# SCH3_Microcontroller.net
KiCad netlist of a schematic drawn in Altium Designer
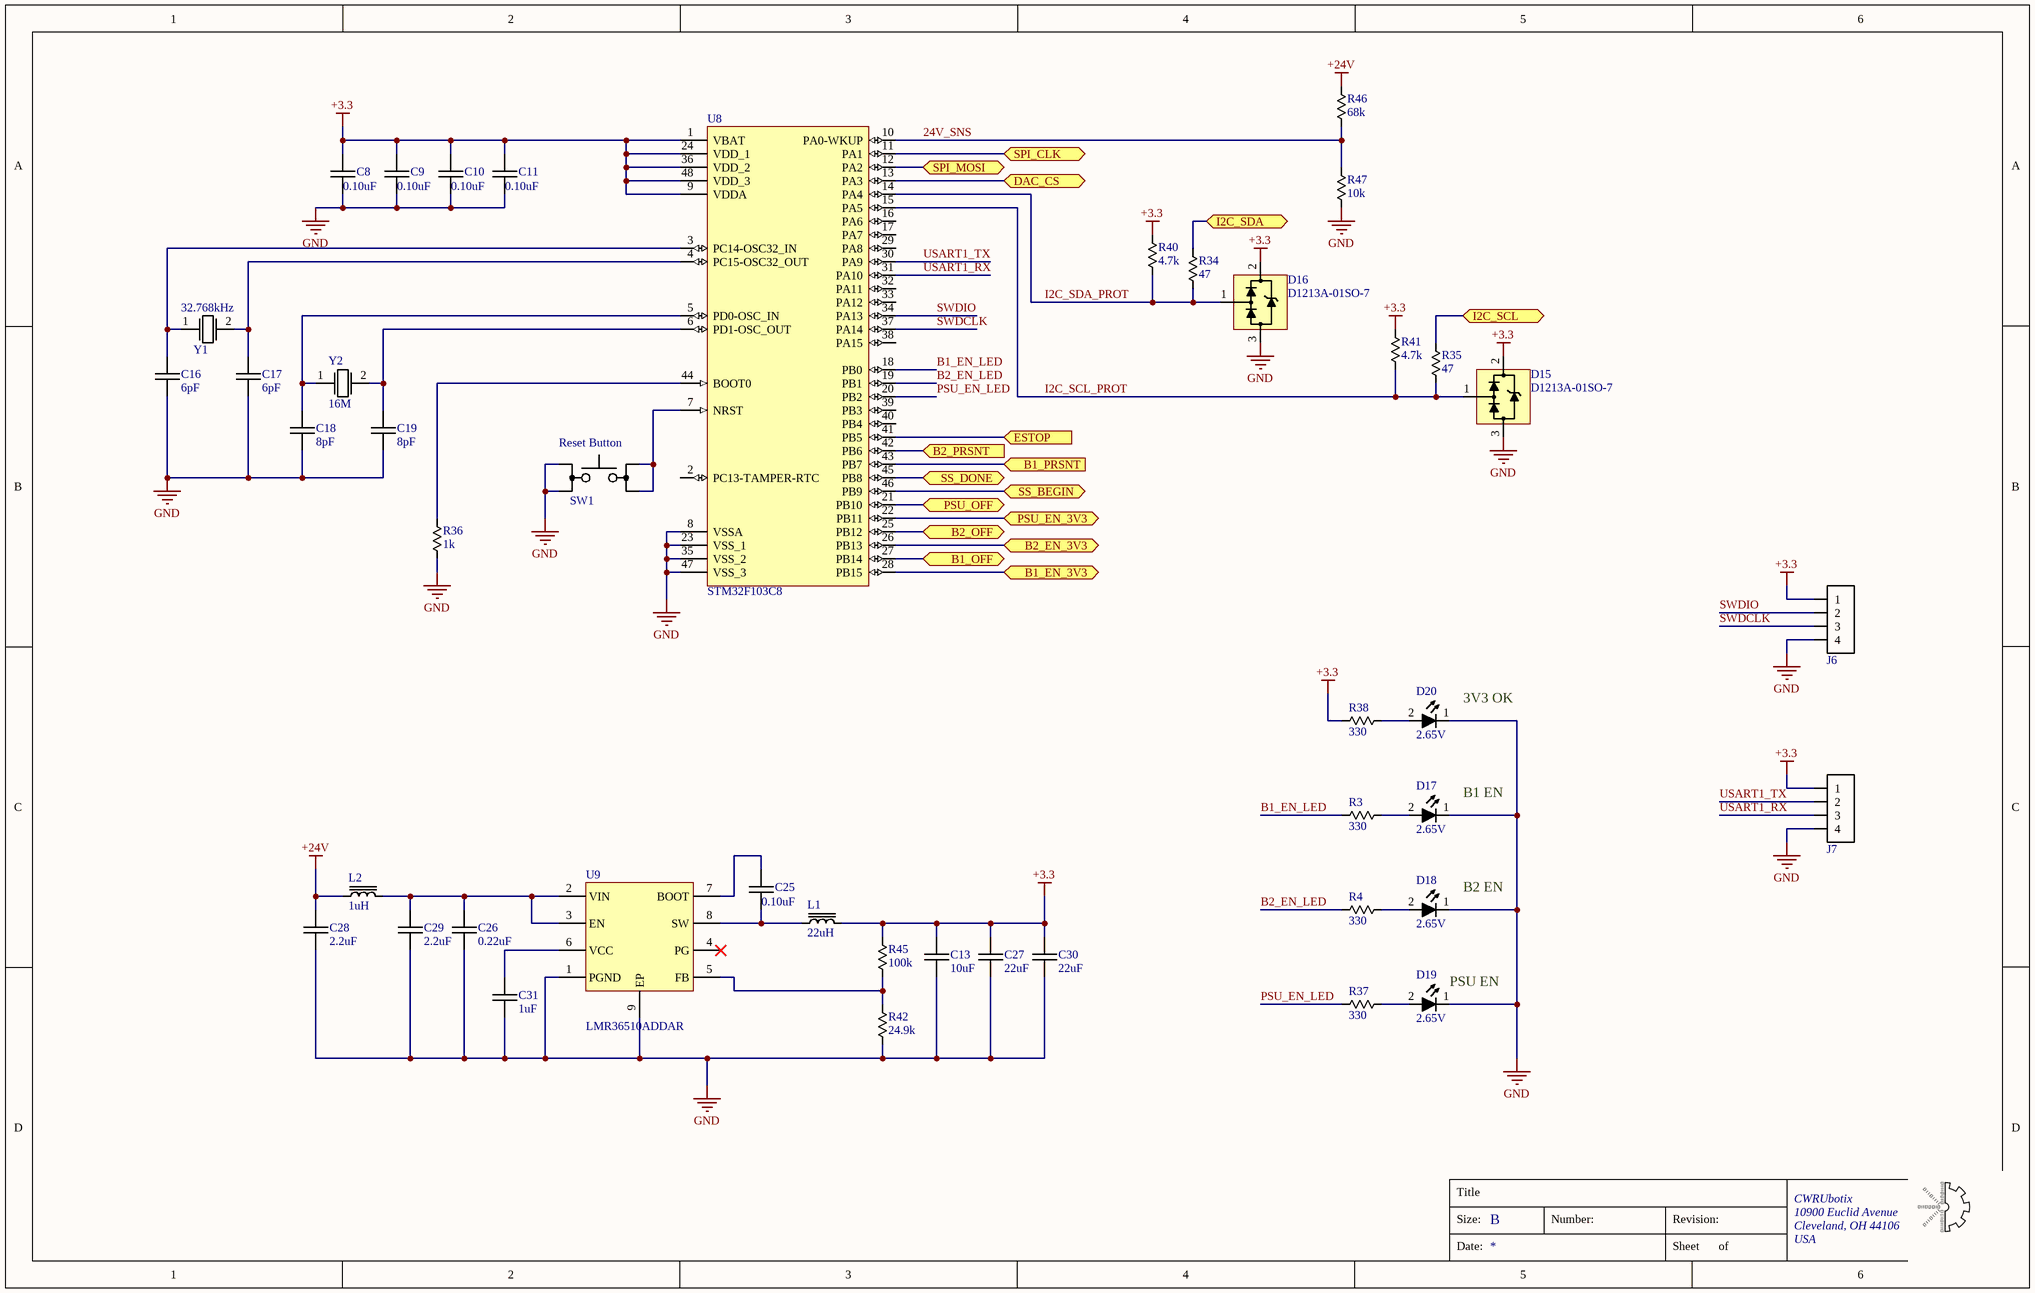
[diagram p0: SCH3_Microcontroller.SchDoc]

(export (version "E")
  (design (tool "Eeschema 10.0.6"))
  (components
    (comp (ref "C8")
      (value "0.10uF")
      (footprint "chip_0805")
      (description "CAP, 0.10uF, 10%, 16V, X7R, 0805")
      (fields (field (name "PART NUMBER") "CAP-00069") (field (name "TOLERANCE") "10%"))
      (libsource (lib "Capacitors$") (part "CAP-00069"))
    )
    (comp (ref "C9")
      (value "0.10uF")
      (footprint "chip_0805")
      (description "CAP, 0.10uF, 10%, 16V, X7R, 0805")
      (fields (field (name "PART NUMBER") "CAP-00069") (field (name "TOLERANCE") "10%"))
      (libsource (lib "Capacitors$") (part "CAP-00069"))
    )
    (comp (ref "C10")
      (value "0.10uF")
      (footprint "chip_0805")
      (description "CAP, 0.10uF, 10%, 16V, X7R, 0805")
      (fields (field (name "PART NUMBER") "CAP-00069") (field (name "TOLERANCE") "10%"))
      (libsource (lib "Capacitors$") (part "CAP-00069"))
    )
    (comp (ref "C11")
      (value "0.10uF")
      (footprint "chip_0805")
      (description "CAP, 0.10uF, 10%, 16V, X7R, 0805")
      (fields (field (name "PART NUMBER") "CAP-00069") (field (name "TOLERANCE") "10%"))
      (libsource (lib "Capacitors$") (part "CAP-00069"))
    )
    (comp (ref "C13")
      (value "10uF")
      (footprint "chip_1206")
      (description "CAP, 10uF, ±10%, 25V, X7R, 1206")
      (fields (field (name "PART NUMBER") "CAP-00539") (field (name "TOLERANCE") "±10%"))
      (libsource (lib "Capacitors$") (part "CAP-00539"))
    )
    (comp (ref "C16")
      (value "6pF")
      (footprint "chip_0603")
      (description "CAP, 6pF, ±10%, 50V, C0G, 0603")
      (fields (field (name "PART NUMBER") "CAP-00538") (field (name "TOLERANCE") "±10%"))
      (libsource (lib "Capacitors$") (part "CAP-00538"))
    )
    (comp (ref "C17")
      (value "6pF")
      (footprint "chip_0603")
      (description "CAP, 6pF, ±10%, 50V, C0G, 0603")
      (fields (field (name "PART NUMBER") "CAP-00538") (field (name "TOLERANCE") "±10%"))
      (libsource (lib "Capacitors$") (part "CAP-00538"))
    )
    (comp (ref "C18")
      (value "8pF")
      (footprint "chip_0603")
      (description "CAP, 8pF, ±0.1pF, 50V, C0G, 0603")
      (fields (field (name "PART NUMBER") "CAP-00402") (field (name "TOLERANCE") "±0.1pF"))
      (libsource (lib "Capacitors$") (part "CAP-00402"))
    )
    (comp (ref "C19")
      (value "8pF")
      (footprint "chip_0603")
      (description "CAP, 8pF, ±0.1pF, 50V, C0G, 0603")
      (fields (field (name "PART NUMBER") "CAP-00402") (field (name "TOLERANCE") "±0.1pF"))
      (libsource (lib "Capacitors$") (part "CAP-00402"))
    )
    (comp (ref "C25")
      (value "0.10uF")
      (footprint "chip_0805")
      (description "CAP, 0.10uF, 10%, 16V, X7R, 0805")
      (fields (field (name "PART NUMBER") "CAP-00069") (field (name "TOLERANCE") "10%"))
      (libsource (lib "Capacitors$") (part "CAP-00069"))
    )
    (comp (ref "C26")
      (value "0.22uF")
      (footprint "chip_0805")
      (description "CAP, 0.22uF, 10%, 100V, X7R, 0805")
      (fields (field (name "PART NUMBER") "CAP-00080") (field (name "TOLERANCE") "10%"))
      (libsource (lib "Capacitors$") (part "CAP-00080"))
    )
    (comp (ref "C27")
      (value "22uF")
      (footprint "chip_1206")
      (description "CAP, 22uF, ±10%, 25V, X5R, 1206")
      (fields (field (name "PART NUMBER") "CAP-00587") (field (name "TOLERANCE") "±10%"))
      (libsource (lib "Capacitors$") (part "CAP-00587"))
    )
    (comp (ref "C28")
      (value "2.2uF")
      (footprint "chip_1206")
      (description "CAP, 2.2uF, ±10%, 50V, X7R, 1206")
      (fields (field (name "PART NUMBER") "CAP-00563") (field (name "TOLERANCE") "±10%"))
      (libsource (lib "Capacitors$") (part "CAP-00563"))
    )
    (comp (ref "C29")
      (value "2.2uF")
      (footprint "chip_1206")
      (description "CAP, 2.2uF, ±10%, 50V, X7R, 1206")
      (fields (field (name "PART NUMBER") "CAP-00563") (field (name "TOLERANCE") "±10%"))
      (libsource (lib "Capacitors$") (part "CAP-00563"))
    )
    (comp (ref "C30")
      (value "22uF")
      (footprint "chip_1206")
      (description "CAP, 22uF, ±10%, 25V, X5R, 1206")
      (fields (field (name "PART NUMBER") "CAP-00587") (field (name "TOLERANCE") "±10%"))
      (libsource (lib "Capacitors$") (part "CAP-00587"))
    )
    (comp (ref "C31")
      (value "1uF")
      (footprint "chip_0805")
      (description "CAP, 1uF, 10%, 16V, X7R, 0805")
      (fields (field (name "PART NUMBER") "CAP-00107") (field (name "TOLERANCE") "10%"))
      (libsource (lib "Capacitors$") (part "CAP-00107"))
    )
    (comp (ref "D15")
      (value "D1213A-01SO-7")
      (footprint "SOT-23-3_1")
      (description "TVS, Rail-Rail Steering + Zener Clamp, 3.3V Standoff, 10V Clamping")
      (fields (field (name "PART NUMBER") "DIO-00075") (field (name "MANUFACTURER") "Diodes Incorporated"))
      (libsource (lib "Diodes$") (part "DIO-00075"))
    )
    (comp (ref "D16")
      (value "D1213A-01SO-7")
      (footprint "SOT-23-3_1")
      (description "TVS, Rail-Rail Steering + Zener Clamp, 3.3V Standoff, 10V Clamping")
      (fields (field (name "PART NUMBER") "DIO-00075") (field (name "MANUFACTURER") "Diodes Incorporated"))
      (libsource (lib "Diodes$") (part "DIO-00075"))
    )
    (comp (ref "D17")
      (value "2.65V")
      (footprint "chip_0603_LED")
      (description "LED, Blue, 0603, Low current, HELI2 Series")
      (fields (field (name "PART NUMBER") "DIO-00049") (field (name "MANUFACTURER") "Kingbright"))
      (libsource (lib "Diodes$") (part "DIO-00049"))
    )
    (comp (ref "D18")
      (value "2.65V")
      (footprint "chip_0603_LED")
      (description "LED, Blue, 0603, Low current, HELI2 Series")
      (fields (field (name "PART NUMBER") "DIO-00049") (field (name "MANUFACTURER") "Kingbright"))
      (libsource (lib "Diodes$") (part "DIO-00049"))
    )
    (comp (ref "D19")
      (value "2.65V")
      (footprint "chip_0603_LED")
      (description "LED, Blue, 0603, Low current, HELI2 Series")
      (fields (field (name "PART NUMBER") "DIO-00049") (field (name "MANUFACTURER") "Kingbright"))
      (libsource (lib "Diodes$") (part "DIO-00049"))
    )
    (comp (ref "D20")
      (value "2.65V")
      (footprint "chip_0603_LED")
      (description "LED, Blue, 0603, Low current, HELI2 Series")
      (fields (field (name "PART NUMBER") "DIO-00049") (field (name "MANUFACTURER") "Kingbright"))
      (libsource (lib "Diodes$") (part "DIO-00049"))
    )
    (comp (ref "J6")
      (value "conn-4x1_0")
      (footprint "HDDR_4x1_0")
      (description "Header 4x1, 0.1\"")
      (fields (field (name "PART NUMBER") "CONN-00029"))
      (libsource (lib "Connectors$") (part "CONN-00029"))
    )
    (comp (ref "J7")
      (value "conn-4x1_0")
      (footprint "HDDR_4x1_0")
      (description "Header 4x1, 0.1\"")
      (fields (field (name "PART NUMBER") "CONN-00029"))
      (libsource (lib "Connectors$") (part "CONN-00029"))
    )
    (comp (ref "L1")
      (value "22uH")
      (footprint "BOURNS_SRN5040")
      (description "Ind, 10uH, 2.1A (2.3A sat.), 0.068 Ohm, SMD")
      (fields (field (name "PART NUMBER") "MAG-00129") (field (name "TOLERANCE") "20%"))
      (libsource (lib "Magnetics$") (part "MAG-00129"))
    )
    (comp (ref "L2")
      (value "1uH")
      (footprint "chip_0805")
      (description "Ind, 1uH, 20%, 900mA, 0805")
      (fields (field (name "PART NUMBER") "MAG-00009") (field (name "TOLERANCE") "20%"))
      (libsource (lib "Magnetics$") (part "MAG-00009"))
    )
    (comp (ref "R3")
      (value "330")
      (footprint "chip_0805")
      (description "RES SMD 330 OHM 1% 1/8W 0805")
      (fields (field (name "PART NUMBER") "RES-00222") (field (name "TOLERANCE") "1%"))
      (libsource (lib "Resistors$") (part "RES-00222"))
    )
    (comp (ref "R4")
      (value "330")
      (footprint "chip_0805")
      (description "RES SMD 330 OHM 1% 1/8W 0805")
      (fields (field (name "PART NUMBER") "RES-00222") (field (name "TOLERANCE") "1%"))
      (libsource (lib "Resistors$") (part "RES-00222"))
    )
    (comp (ref "R34")
      (value "47")
      (footprint "chip_0805")
      (description "RES SMD 47 OHM 1% 1/8W 0805")
      (fields (field (name "PART NUMBER") "RES-00154") (field (name "TOLERANCE") "1%"))
      (libsource (lib "Resistors$") (part "RES-00154"))
    )
    (comp (ref "R35")
      (value "47")
      (footprint "chip_0805")
      (description "RES SMD 47 OHM 1% 1/8W 0805")
      (fields (field (name "PART NUMBER") "RES-00154") (field (name "TOLERANCE") "1%"))
      (libsource (lib "Resistors$") (part "RES-00154"))
    )
    (comp (ref "R36")
      (value "1k")
      (footprint "chip_0805")
      (description "RES SMD 1K OHM 1% 1/8W 0805")
      (fields (field (name "PART NUMBER") "RES-00361") (field (name "TOLERANCE") "1%"))
      (libsource (lib "Resistors$") (part "RES-00361"))
    )
    (comp (ref "R37")
      (value "330")
      (footprint "chip_0805")
      (description "RES SMD 330 OHM 1% 1/8W 0805")
      (fields (field (name "PART NUMBER") "RES-00222") (field (name "TOLERANCE") "1%"))
      (libsource (lib "Resistors$") (part "RES-00222"))
    )
    (comp (ref "R38")
      (value "330")
      (footprint "chip_0805")
      (description "RES SMD 330 OHM 1% 1/8W 0805")
      (fields (field (name "PART NUMBER") "RES-00222") (field (name "TOLERANCE") "1%"))
      (libsource (lib "Resistors$") (part "RES-00222"))
    )
    (comp (ref "R40")
      (value "4.7k")
      (footprint "chip_0805")
      (description "RES SMD 4.7K OHM 1% 1/8W 0805")
      (fields (field (name "PART NUMBER") "RES-00471") (field (name "TOLERANCE") "1%"))
      (libsource (lib "Resistors$") (part "RES-00471"))
    )
    (comp (ref "R41")
      (value "4.7k")
      (footprint "chip_0805")
      (description "RES SMD 4.7K OHM 1% 1/8W 0805")
      (fields (field (name "PART NUMBER") "RES-00471") (field (name "TOLERANCE") "1%"))
      (libsource (lib "Resistors$") (part "RES-00471"))
    )
    (comp (ref "R42")
      (value "24.9k")
      (footprint "chip_0805")
      (description "RES SMD 24.9K OHM 1% 1/8W 0805")
      (fields (field (name "PART NUMBER") "RES-00396") (field (name "TOLERANCE") "1%"))
      (libsource (lib "Resistors$") (part "RES-00396"))
    )
    (comp (ref "R45")
      (value "100k")
      (footprint "chip_0805")
      (description "RES SMD 100K OHM 1% 1/8W 0805")
      (fields (field (name "PART NUMBER") "RES-00302") (field (name "TOLERANCE") "1%"))
      (libsource (lib "Resistors$") (part "RES-00302"))
    )
    (comp (ref "R46")
      (value "68k")
      (footprint "chip_0805")
      (description "RES SMD 68K OHM 1% 1/8W 0805 100ppm")
      (fields (field (name "PART NUMBER") "RES-00724") (field (name "TOLERANCE") "1%"))
      (libsource (lib "Resistors$") (part "RES-00724"))
    )
    (comp (ref "R47")
      (value "10k")
      (footprint "chip_0805")
      (description "RES SMD 10K OHM 1% 1/8W 0805")
      (fields (field (name "PART NUMBER") "RES-00307") (field (name "TOLERANCE") "1%"))
      (libsource (lib "Resistors$") (part "RES-00307"))
    )
    (comp (ref "SW1")
      (value "SW_1P1T_2")
      (footprint "TE_CONN_3-1825910-5")
      (description "Switch, Tactile, SPST-NO, 50mA 24V, Vertical, Thru-Hole")
      (fields (field (name "PART NUMBER") "MISC-00059") (field (name "MANUFACTURER") "TE Connectivity"))
      (libsource (lib "Misc$") (part "MISC-00059"))
    )
    (comp (ref "U8")
      (value "STM32F103C8")
      (footprint "LQFP48_0")
      (description "STM32 M3, LQFP-48")
      (fields (field (name "PART NUMBER") "UCTRL-00008") (field (name "MANUFACTURER") "ST"))
      (libsource (lib "Microcontrollers$") (part "UCTRL-00008"))
    )
    (comp (ref "U9")
      (value "LMR36510ADDAR")
      (footprint "SO-8_PPAD")
      (description "REG, Synchronous Buck, 4.2V~65V, 1A, Simple Switcher")
      (fields (field (name "PART NUMBER") "PWREG-00076") (field (name "MANUFACTURER") "TI"))
      (libsource (lib "Power Reg$") (part "PWREG-00076"))
    )
    (comp (ref "Y1")
      (value "osc_xtal_2p_0")
      (footprint "ABS25_OSC")
      (description "XTAL, 32.768kHz, 6pF, 20ppm")
      (fields (field (name "PART NUMBER") "OSC-00003") (field (name "TOLERANCE") "20ppm"))
      (libsource (lib "Oscillators$") (part "OSC-00003"))
    )
    (comp (ref "Y2")
      (value "16M")
      (footprint "NX5032GA")
      (description "XTAL, 16MHz, 8pF, 50, 20ppm")
      (fields (field (name "PART NUMBER") "OSC-00000") (field (name "TOLERANCE") "20ppm"))
      (libsource (lib "Oscillators$") (part "OSC-00000"))
    )
  )
  (nets
    (net (code "1") (name "+3.3") (class "Default")
      (node (ref "C10") (pin "1") (pinfunction "1_1") (pintype "passive"))
      (node (ref "C11") (pin "1") (pinfunction "1_1") (pintype "passive"))
      (node (ref "C13") (pin "1") (pinfunction "1_1") (pintype "passive"))
      (node (ref "C27") (pin "1") (pinfunction "1_1") (pintype "passive"))
      (node (ref "C30") (pin "1") (pinfunction "1_1") (pintype "passive"))
      (node (ref "C8") (pin "1") (pinfunction "1_1") (pintype "passive"))
      (node (ref "C9") (pin "1") (pinfunction "1_1") (pintype "passive"))
      (node (ref "D15") (pin "2") (pinfunction "VCC_2") (pintype "passive"))
      (node (ref "D16") (pin "2") (pinfunction "VCC_2") (pintype "passive"))
      (node (ref "J6") (pin "1") (pinfunction "1_1") (pintype "passive"))
      (node (ref "J7") (pin "1") (pinfunction "1_1") (pintype "passive"))
      (node (ref "L1") (pin "2") (pinfunction "2_2") (pintype "passive"))
      (node (ref "R38") (pin "1") (pinfunction "1_1") (pintype "passive"))
      (node (ref "R40") (pin "1") (pinfunction "1_1") (pintype "passive"))
      (node (ref "R41") (pin "1") (pinfunction "1_1") (pintype "passive"))
      (node (ref "R45") (pin "2") (pinfunction "2_2") (pintype "passive"))
      (node (ref "U8") (pin "1") (pinfunction "VBAT_1") (pintype "passive"))
      (node (ref "U8") (pin "24") (pinfunction "VDD_1_24") (pintype "power_in"))
      (node (ref "U8") (pin "36") (pinfunction "VDD_2_36") (pintype "power_in"))
      (node (ref "U8") (pin "48") (pinfunction "VDD_3_48") (pintype "power_in"))
      (node (ref "U8") (pin "9") (pinfunction "VDDA_9") (pintype "power_in"))
    )
    (net (code "2") (name "+24V") (class "Default")
      (node (ref "C28") (pin "1") (pinfunction "1_1") (pintype "passive"))
      (node (ref "L2") (pin "1") (pinfunction "1_1") (pintype "passive"))
      (node (ref "R46") (pin "1") (pinfunction "1_1") (pintype "passive"))
    )
    (net (code "3") (name "/24V_SNS") (class "Default")
      (node (ref "R46") (pin "2") (pinfunction "2_2") (pintype "passive"))
      (node (ref "R47") (pin "1") (pinfunction "1_1") (pintype "passive"))
      (node (ref "U8") (pin "10") (pinfunction "PA0-WKUP_10") (pintype "bidirectional"))
    )
    (net (code "4") (name "/B1_EN_3V3") (class "Default")
      (node (ref "U8") (pin "28") (pinfunction "PB15_28") (pintype "bidirectional"))
    )
    (net (code "5") (name "/B1_EN_LED") (class "Default")
      (node (ref "R3") (pin "1") (pinfunction "1_1") (pintype "passive"))
      (node (ref "U8") (pin "18") (pinfunction "PB0_18") (pintype "bidirectional"))
    )
    (net (code "6") (name "/B1_OFF") (class "Default")
      (node (ref "U8") (pin "27") (pinfunction "PB14_27") (pintype "bidirectional"))
    )
    (net (code "7") (name "/B1_PRSNT") (class "Default")
      (node (ref "U8") (pin "43") (pinfunction "PB7_43") (pintype "bidirectional"))
    )
    (net (code "8") (name "/B2_EN_3V3") (class "Default")
      (node (ref "U8") (pin "26") (pinfunction "PB13_26") (pintype "bidirectional"))
    )
    (net (code "9") (name "/B2_EN_LED") (class "Default")
      (node (ref "R4") (pin "1") (pinfunction "1_1") (pintype "passive"))
      (node (ref "U8") (pin "19") (pinfunction "PB1_19") (pintype "bidirectional"))
    )
    (net (code "10") (name "/B2_OFF") (class "Default")
      (node (ref "U8") (pin "25") (pinfunction "PB12_25") (pintype "bidirectional"))
    )
    (net (code "11") (name "/B2_PRSNT") (class "Default")
      (node (ref "U8") (pin "42") (pinfunction "PB6_42") (pintype "bidirectional"))
    )
    (net (code "12") (name "/DAC_CS") (class "Default")
      (node (ref "U8") (pin "13") (pinfunction "PA3_13") (pintype "bidirectional"))
    )
    (net (code "13") (name "/ESTOP") (class "Default")
      (node (ref "U8") (pin "41") (pinfunction "PB5_41") (pintype "bidirectional"))
    )
    (net (code "14") (name "/I2C_SCL") (class "Default")
      (node (ref "R35") (pin "2") (pinfunction "2_2") (pintype "passive"))
    )
    (net (code "15") (name "/I2C_SCL_PROT") (class "Default")
      (node (ref "D15") (pin "1") (pinfunction "LINE_1") (pintype "passive"))
      (node (ref "R35") (pin "1") (pinfunction "1_1") (pintype "passive"))
      (node (ref "R41") (pin "2") (pinfunction "2_2") (pintype "passive"))
      (node (ref "U8") (pin "15") (pinfunction "PA5_15") (pintype "bidirectional"))
    )
    (net (code "16") (name "/I2C_SDA") (class "Default")
      (node (ref "R34") (pin "2") (pinfunction "2_2") (pintype "passive"))
    )
    (net (code "17") (name "/I2C_SDA_PROT") (class "Default")
      (node (ref "D16") (pin "1") (pinfunction "LINE_1") (pintype "passive"))
      (node (ref "R34") (pin "1") (pinfunction "1_1") (pintype "passive"))
      (node (ref "R40") (pin "2") (pinfunction "2_2") (pintype "passive"))
      (node (ref "U8") (pin "14") (pinfunction "PA4_14") (pintype "bidirectional"))
    )
    (net (code "18") (name "/PSU_EN_3V3") (class "Default")
      (node (ref "U8") (pin "22") (pinfunction "PB11_22") (pintype "bidirectional"))
    )
    (net (code "19") (name "/PSU_EN_LED") (class "Default")
      (node (ref "R37") (pin "1") (pinfunction "1_1") (pintype "passive"))
      (node (ref "U8") (pin "20") (pinfunction "PB2_20") (pintype "bidirectional"))
    )
    (net (code "20") (name "/PSU_OFF") (class "Default")
      (node (ref "U8") (pin "21") (pinfunction "PB10_21") (pintype "bidirectional"))
    )
    (net (code "21") (name "/SPI_CLK") (class "Default")
      (node (ref "U8") (pin "11") (pinfunction "PA1_11") (pintype "bidirectional"))
    )
    (net (code "22") (name "/SPI_MOSI") (class "Default")
      (node (ref "U8") (pin "12") (pinfunction "PA2_12") (pintype "bidirectional"))
    )
    (net (code "23") (name "/SS_BEGIN") (class "Default")
      (node (ref "U8") (pin "46") (pinfunction "PB9_46") (pintype "bidirectional"))
    )
    (net (code "24") (name "/SS_DONE") (class "Default")
      (node (ref "U8") (pin "45") (pinfunction "PB8_45") (pintype "bidirectional"))
    )
    (net (code "25") (name "/SWDCLK") (class "Default")
      (node (ref "J6") (pin "3") (pinfunction "3_3") (pintype "passive"))
      (node (ref "U8") (pin "37") (pinfunction "PA14_37") (pintype "bidirectional"))
    )
    (net (code "26") (name "/SWDIO") (class "Default")
      (node (ref "J6") (pin "2") (pinfunction "2_2") (pintype "passive"))
      (node (ref "U8") (pin "34") (pinfunction "PA13_34") (pintype "bidirectional"))
    )
    (net (code "27") (name "/USART1_RX") (class "Default")
      (node (ref "J7") (pin "3") (pinfunction "3_3") (pintype "passive"))
      (node (ref "U8") (pin "31") (pinfunction "PA10_31") (pintype "bidirectional"))
    )
    (net (code "28") (name "/USART1_TX") (class "Default")
      (node (ref "J7") (pin "2") (pinfunction "2_2") (pintype "passive"))
      (node (ref "U8") (pin "30") (pinfunction "PA9_30") (pintype "bidirectional"))
    )
    (net (code "29") (name "GND") (class "Default")
      (node (ref "C10") (pin "2") (pinfunction "2_2") (pintype "passive"))
      (node (ref "C11") (pin "2") (pinfunction "2_2") (pintype "passive"))
      (node (ref "C13") (pin "2") (pinfunction "2_2") (pintype "passive"))
      (node (ref "C16") (pin "2") (pinfunction "2_2") (pintype "passive"))
      (node (ref "C17") (pin "2") (pinfunction "2_2") (pintype "passive"))
      (node (ref "C18") (pin "2") (pinfunction "2_2") (pintype "passive"))
      (node (ref "C19") (pin "2") (pinfunction "2_2") (pintype "passive"))
      (node (ref "C26") (pin "2") (pinfunction "2_2") (pintype "passive"))
      (node (ref "C27") (pin "2") (pinfunction "2_2") (pintype "passive"))
      (node (ref "C28") (pin "2") (pinfunction "2_2") (pintype "passive"))
      (node (ref "C29") (pin "2") (pinfunction "2_2") (pintype "passive"))
      (node (ref "C30") (pin "2") (pinfunction "2_2") (pintype "passive"))
      (node (ref "C31") (pin "2") (pinfunction "2_2") (pintype "passive"))
      (node (ref "C8") (pin "2") (pinfunction "2_2") (pintype "passive"))
      (node (ref "C9") (pin "2") (pinfunction "2_2") (pintype "passive"))
      (node (ref "D15") (pin "3") (pinfunction "GND_3") (pintype "passive"))
      (node (ref "D16") (pin "3") (pinfunction "GND_3") (pintype "passive"))
      (node (ref "D17") (pin "1") (pinfunction "1_1") (pintype "passive"))
      (node (ref "D18") (pin "1") (pinfunction "1_1") (pintype "passive"))
      (node (ref "D19") (pin "1") (pinfunction "1_1") (pintype "passive"))
      (node (ref "D20") (pin "1") (pinfunction "1_1") (pintype "passive"))
      (node (ref "J6") (pin "4") (pinfunction "4_4") (pintype "passive"))
      (node (ref "J7") (pin "4") (pinfunction "4_4") (pintype "passive"))
      (node (ref "R36") (pin "2") (pinfunction "2_2") (pintype "passive"))
      (node (ref "R42") (pin "2") (pinfunction "2_2") (pintype "passive"))
      (node (ref "R47") (pin "2") (pinfunction "2_2") (pintype "passive"))
      (node (ref "SW1") (pin "1") (pinfunction "1_1") (pintype "passive"))
      (node (ref "SW1") (pin "2") (pinfunction "2_2") (pintype "passive"))
      (node (ref "U8") (pin "23") (pinfunction "VSS_1_23") (pintype "power_in"))
      (node (ref "U8") (pin "35") (pinfunction "VSS_2_35") (pintype "power_in"))
      (node (ref "U8") (pin "47") (pinfunction "VSS_3_47") (pintype "power_in"))
      (node (ref "U8") (pin "8") (pinfunction "VSSA_8") (pintype "power_in"))
      (node (ref "U9") (pin "1") (pinfunction "PGND_1") (pintype "passive"))
      (node (ref "U9") (pin "9") (pinfunction "EP_9") (pintype "passive"))
    )
    (net (code "30") (name "Net-(D17-Pad2)") (class "Default")
      (node (ref "D17") (pin "2") (pinfunction "2_2") (pintype "passive"))
      (node (ref "R3") (pin "2") (pinfunction "2_2") (pintype "passive"))
    )
    (net (code "31") (name "Net-(D18-Pad2)") (class "Default")
      (node (ref "D18") (pin "2") (pinfunction "2_2") (pintype "passive"))
      (node (ref "R4") (pin "2") (pinfunction "2_2") (pintype "passive"))
    )
    (net (code "32") (name "Net-(D19-Pad2)") (class "Default")
      (node (ref "D19") (pin "2") (pinfunction "2_2") (pintype "passive"))
      (node (ref "R37") (pin "2") (pinfunction "2_2") (pintype "passive"))
    )
    (net (code "33") (name "Net-(D20-Pad2)") (class "Default")
      (node (ref "D20") (pin "2") (pinfunction "2_2") (pintype "passive"))
      (node (ref "R38") (pin "2") (pinfunction "2_2") (pintype "passive"))
    )
    (net (code "34") (name "Net-(U8-BOOT0)") (class "Default")
      (node (ref "R36") (pin "1") (pinfunction "1_1") (pintype "passive"))
      (node (ref "U8") (pin "44") (pinfunction "BOOT0_44") (pintype "input"))
    )
    (net (code "35") (name "Net-(U8-NRST)") (class "Default")
      (node (ref "SW1") (pin "3") (pinfunction "3_3") (pintype "passive"))
      (node (ref "SW1") (pin "4") (pinfunction "4_4") (pintype "passive"))
      (node (ref "U8") (pin "7") (pinfunction "NRST_7") (pintype "input"))
    )
    (net (code "36") (name "Net-(U8-PC14-OSC32_IN)") (class "Default")
      (node (ref "C16") (pin "1") (pinfunction "1_1") (pintype "passive"))
      (node (ref "U8") (pin "3") (pinfunction "PC14-OSC32_IN_3") (pintype "bidirectional"))
      (node (ref "Y1") (pin "1") (pinfunction "20_1") (pintype "passive"))
    )
    (net (code "37") (name "Net-(U8-PC15-OSC32_OUT)") (class "Default")
      (node (ref "C17") (pin "1") (pinfunction "1_1") (pintype "passive"))
      (node (ref "U8") (pin "4") (pinfunction "PC15-OSC32_OUT_4") (pintype "bidirectional"))
      (node (ref "Y1") (pin "2") (pinfunction "20_2") (pintype "passive"))
    )
    (net (code "38") (name "Net-(U8-PD0-OSC_IN)") (class "Default")
      (node (ref "C18") (pin "1") (pinfunction "1_1") (pintype "passive"))
      (node (ref "U8") (pin "5") (pinfunction "PD0-OSC_IN_5") (pintype "bidirectional"))
      (node (ref "Y2") (pin "1") (pinfunction "20_1") (pintype "passive"))
    )
    (net (code "39") (name "Net-(U8-PD1-OSC_OUT)") (class "Default")
      (node (ref "C19") (pin "1") (pinfunction "1_1") (pintype "passive"))
      (node (ref "U8") (pin "6") (pinfunction "PD1-OSC_OUT_6") (pintype "bidirectional"))
      (node (ref "Y2") (pin "2") (pinfunction "20_2") (pintype "passive"))
    )
    (net (code "40") (name "Net-(U9-BOOT)") (class "Default")
      (node (ref "C25") (pin "1") (pinfunction "1_1") (pintype "passive"))
      (node (ref "U9") (pin "7") (pinfunction "BOOT_7") (pintype "passive"))
    )
    (net (code "41") (name "Net-(U9-EN)") (class "Default")
      (node (ref "C26") (pin "1") (pinfunction "1_1") (pintype "passive"))
      (node (ref "C29") (pin "1") (pinfunction "1_1") (pintype "passive"))
      (node (ref "L2") (pin "2") (pinfunction "2_2") (pintype "passive"))
      (node (ref "U9") (pin "2") (pinfunction "VIN_2") (pintype "passive"))
      (node (ref "U9") (pin "3") (pinfunction "EN_3") (pintype "passive"))
    )
    (net (code "42") (name "Net-(U9-FB)") (class "Default")
      (node (ref "R42") (pin "1") (pinfunction "1_1") (pintype "passive"))
      (node (ref "R45") (pin "1") (pinfunction "1_1") (pintype "passive"))
      (node (ref "U9") (pin "5") (pinfunction "FB_5") (pintype "passive"))
    )
    (net (code "43") (name "Net-(U9-SW)") (class "Default")
      (node (ref "C25") (pin "2") (pinfunction "2_2") (pintype "passive"))
      (node (ref "L1") (pin "1") (pinfunction "1_1") (pintype "passive"))
      (node (ref "U9") (pin "8") (pinfunction "SW_8") (pintype "passive"))
    )
    (net (code "44") (name "Net-(U9-VCC)") (class "Default")
      (node (ref "C31") (pin "1") (pinfunction "1_1") (pintype "passive"))
      (node (ref "U9") (pin "6") (pinfunction "VCC_6") (pintype "passive"))
    )
    (net (code "45") (name "unconnected-(U8-PA6-Pad16)") (class "Default")
      (node (ref "U8") (pin "16") (pinfunction "PA6_16") (pintype "bidirectional"))
    )
    (net (code "46") (name "unconnected-(U8-PA7-Pad17)") (class "Default")
      (node (ref "U8") (pin "17") (pinfunction "PA7_17") (pintype "bidirectional"))
    )
    (net (code "47") (name "unconnected-(U8-PA8-Pad29)") (class "Default")
      (node (ref "U8") (pin "29") (pinfunction "PA8_29") (pintype "bidirectional"))
    )
    (net (code "48") (name "unconnected-(U8-PA11-Pad32)") (class "Default")
      (node (ref "U8") (pin "32") (pinfunction "PA11_32") (pintype "bidirectional"))
    )
    (net (code "49") (name "unconnected-(U8-PA12-Pad33)") (class "Default")
      (node (ref "U8") (pin "33") (pinfunction "PA12_33") (pintype "bidirectional"))
    )
    (net (code "50") (name "unconnected-(U8-PA15-Pad38)") (class "Default")
      (node (ref "U8") (pin "38") (pinfunction "PA15_38") (pintype "bidirectional"))
    )
    (net (code "51") (name "unconnected-(U8-PB3-Pad39)") (class "Default")
      (node (ref "U8") (pin "39") (pinfunction "PB3_39") (pintype "bidirectional"))
    )
    (net (code "52") (name "unconnected-(U8-PB4-Pad40)") (class "Default")
      (node (ref "U8") (pin "40") (pinfunction "PB4_40") (pintype "bidirectional"))
    )
    (net (code "53") (name "unconnected-(U8-PC13-TAMPER-RTC-Pad2)") (class "Default")
      (node (ref "U8") (pin "2") (pinfunction "PC13-TAMPER-RTC_2") (pintype "bidirectional"))
    )
    (net (code "54") (name "unconnected-(U9-PG-Pad4)") (class "Default")
      (node (ref "U9") (pin "4") (pinfunction "PG_4") (pintype "passive+no_connect"))
    )
  )
)
